# Sensor_Coup_Amp.net
KiCad netlist of a schematic drawn in Altium Designer
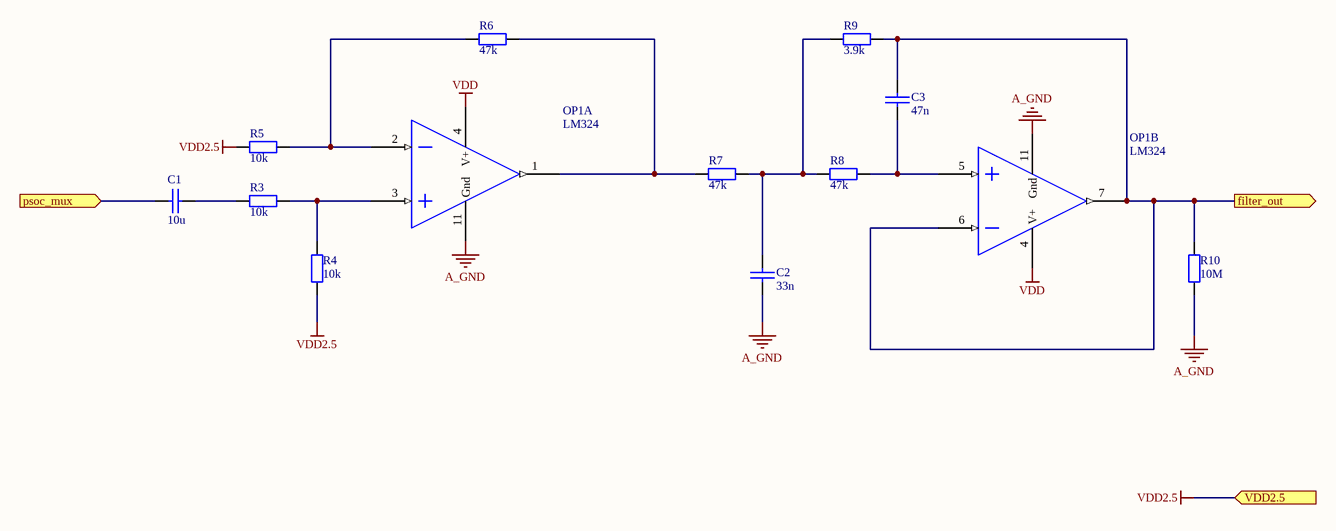
[diagram p0: Sensor_Coup_Amp.SchDoc]

(export (version "E")
  (design (tool "Eeschema 10.0.6"))
  (components
    (comp (ref "C1") (value "10u") (description "Capacitor") (libsource (lib "EceParts") (part "Cap")))
    (comp (ref "C2") (value "33n") (description "Capacitor") (libsource (lib "EceParts") (part "Cap")))
    (comp (ref "C3") (value "47n") (description "Capacitor") (libsource (lib "EceParts") (part "Cap")))
    (comp (ref "OP1") (value "LM324") (libsource (lib "EceParts") (part "LM324")))
    (comp (ref "R3") (value "10k") (description "Resistor") (libsource (lib "EceParts") (part "Resistor")))
    (comp (ref "R4") (value "10k") (description "Resistor") (libsource (lib "") (part "Resistor_1")))
    (comp (ref "R5") (value "10k") (description "Resistor") (libsource (lib "EceParts") (part "Resistor")))
    (comp (ref "R6") (value "47k") (description "Resistor") (libsource (lib "EceParts") (part "Resistor")))
    (comp (ref "R7") (value "47k") (description "Resistor") (libsource (lib "EceParts") (part "Resistor")))
    (comp (ref "R8") (value "47k") (description "Resistor") (libsource (lib "EceParts") (part "Resistor")))
    (comp (ref "R9") (value "3.9k") (description "Resistor") (libsource (lib "EceParts") (part "Resistor")))
    (comp (ref "R10") (value "10M") (description "Resistor") (libsource (lib "") (part "Resistor_1")))
  )
  (nets
    (net (code "1") (name "/filter_out") (class "Default")
      (node (ref "C3") (pin "2") (pinfunction "2_2") (pintype "passive"))
      (node (ref "OP1") (pin "6") (pinfunction "IN2(-)_6") (pintype "input"))
      (node (ref "OP1") (pin "7") (pinfunction "OUT2_7") (pintype "output"))
      (node (ref "R10") (pin "2") (pinfunction "2_2") (pintype "passive"))
      (node (ref "R9") (pin "2") (pinfunction "2_2") (pintype "passive"))
    )
    (net (code "2") (name "/psoc_mux") (class "Default")
      (node (ref "C1") (pin "1") (pinfunction "1_1") (pintype "passive"))
    )
    (net (code "3") (name "A_GND") (class "Default")
      (node (ref "C2") (pin "1") (pinfunction "1_1") (pintype "passive"))
      (node (ref "OP1") (pin "11") (pinfunction "Gnd_11") (pintype "power_in"))
      (node (ref "R10") (pin "1") (pinfunction "1_1") (pintype "passive"))
    )
    (net (code "4") (name "Net-(C1-Pad2)") (class "Default")
      (node (ref "C1") (pin "2") (pinfunction "2_2") (pintype "passive"))
      (node (ref "R3") (pin "1") (pinfunction "1_1") (pintype "passive"))
    )
    (net (code "5") (name "Net-(C2-Pad2)") (class "Default")
      (node (ref "C2") (pin "2") (pinfunction "2_2") (pintype "passive"))
      (node (ref "R7") (pin "2") (pinfunction "2_2") (pintype "passive"))
      (node (ref "R8") (pin "1") (pinfunction "1_1") (pintype "passive"))
      (node (ref "R9") (pin "1") (pinfunction "1_1") (pintype "passive"))
    )
    (net (code "6") (name "Net-(OP1A-IN1(+))") (class "Default")
      (node (ref "OP1") (pin "3") (pinfunction "IN1(+)_3") (pintype "input"))
      (node (ref "R3") (pin "2") (pinfunction "2_2") (pintype "passive"))
      (node (ref "R4") (pin "2") (pinfunction "2_2") (pintype "passive"))
    )
    (net (code "7") (name "Net-(OP1A-IN1(-))") (class "Default")
      (node (ref "OP1") (pin "2") (pinfunction "IN1(-)_2") (pintype "input"))
      (node (ref "R5") (pin "2") (pinfunction "2_2") (pintype "passive"))
      (node (ref "R6") (pin "1") (pinfunction "1_1") (pintype "passive"))
    )
    (net (code "8") (name "Net-(OP1A-OUT1)") (class "Default")
      (node (ref "OP1") (pin "1") (pinfunction "OUT1_1") (pintype "output"))
      (node (ref "R6") (pin "2") (pinfunction "2_2") (pintype "passive"))
      (node (ref "R7") (pin "1") (pinfunction "1_1") (pintype "passive"))
    )
    (net (code "9") (name "Net-(OP1B-IN2+))") (class "Default")
      (node (ref "C3") (pin "1") (pinfunction "1_1") (pintype "passive"))
      (node (ref "OP1") (pin "5") (pinfunction "IN2+)_5") (pintype "input"))
      (node (ref "R8") (pin "2") (pinfunction "2_2") (pintype "passive"))
    )
    (net (code "10") (name "VDD") (class "Default")
      (node (ref "OP1") (pin "4") (pinfunction "V+_4") (pintype "power_in"))
    )
    (net (code "11") (name "VDD2.5") (class "Default")
      (node (ref "R4") (pin "1") (pinfunction "1_1") (pintype "passive"))
      (node (ref "R5") (pin "1") (pinfunction "1_1") (pintype "passive"))
    )
  )
)
